# LC_to_ADC.net
KiCad netlist of a schematic drawn in Altium Designer
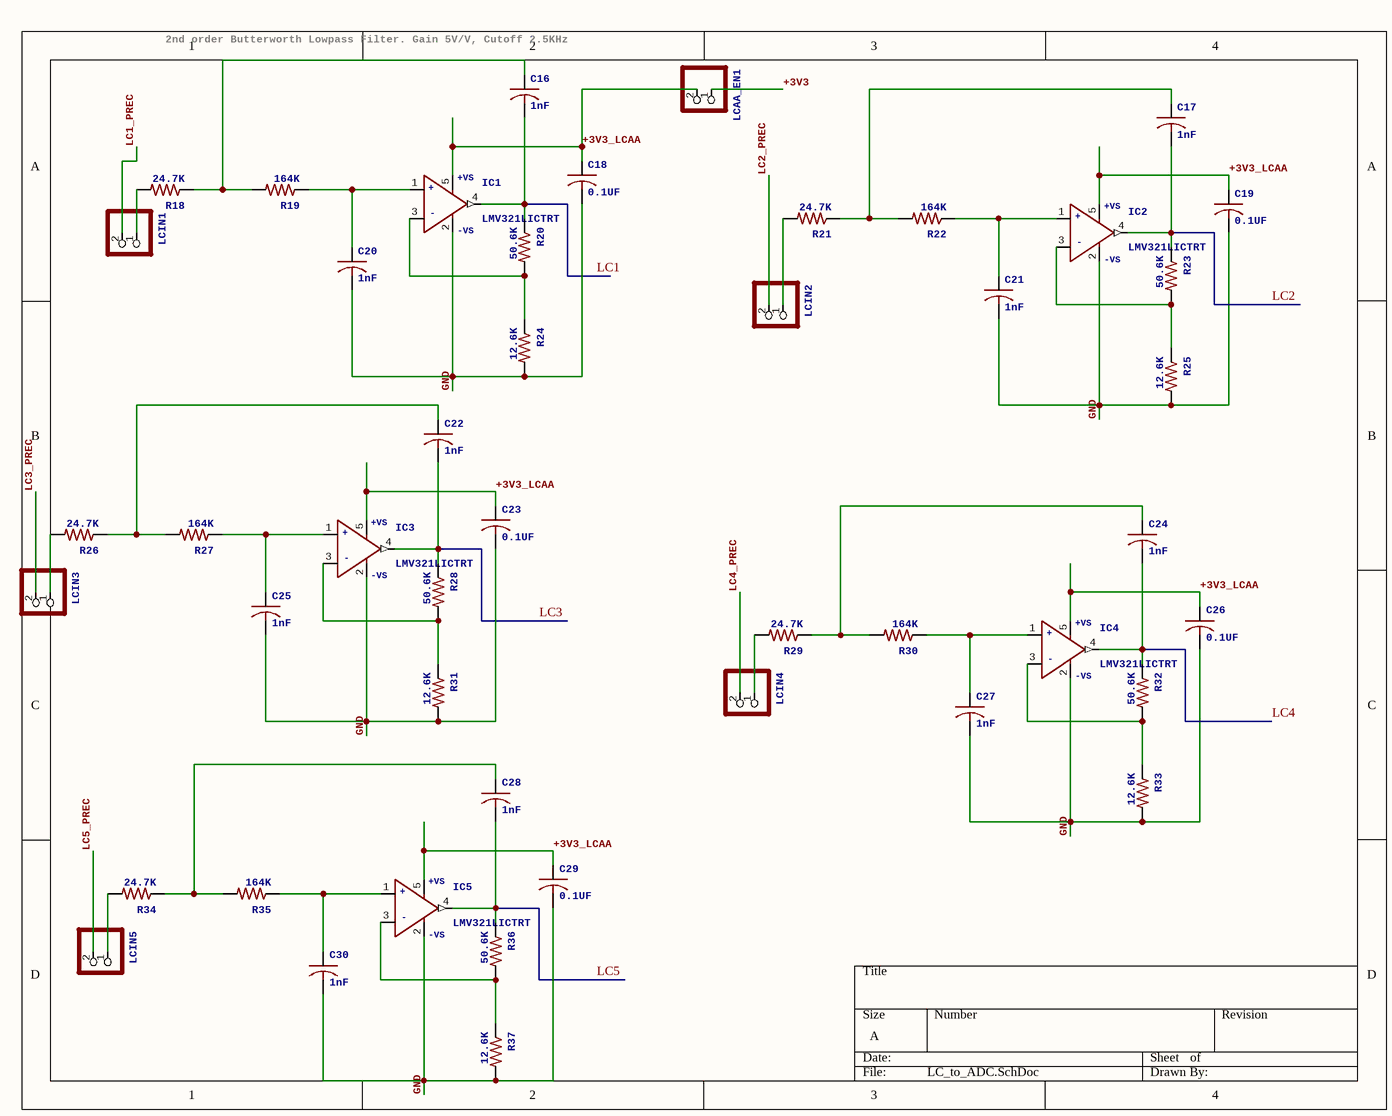
[diagram p0: LC_to_ADC.SchDoc]

(export (version "E")
  (design (tool "Eeschema 10.0.6"))
  (components
    (comp (ref "C16")
      (value "1nF")
      (footprint "CAPCP2012X06N")
      (description "CAPACITOR, American symbol")
      (libsource (lib "rcl") (part "C-USC0805"))
    )
    (comp (ref "C17")
      (value "1nF")
      (footprint "CAPCP2012X06N")
      (description "CAPACITOR, American symbol")
      (libsource (lib "rcl") (part "C-USC0805"))
    )
    (comp (ref "C18")
      (value "0.1UF")
      (footprint "CAPCP2012X06N")
      (description "CAPACITOR, American symbol")
      (libsource (lib "rcl") (part "C-USC0805"))
    )
    (comp (ref "C19")
      (value "0.1UF")
      (footprint "CAPCP2012X06N")
      (description "CAPACITOR, American symbol")
      (libsource (lib "rcl") (part "C-USC0805"))
    )
    (comp (ref "C20")
      (value "1nF")
      (footprint "CAPCP2012X06N")
      (description "CAPACITOR, American symbol")
      (libsource (lib "rcl") (part "C-USC0805"))
    )
    (comp (ref "C21")
      (value "1nF")
      (footprint "CAPCP2012X06N")
      (description "CAPACITOR, American symbol")
      (libsource (lib "rcl") (part "C-USC0805"))
    )
    (comp (ref "C22")
      (value "1nF")
      (footprint "CAPCP2012X06N")
      (description "CAPACITOR, American symbol")
      (libsource (lib "rcl") (part "C-USC0805"))
    )
    (comp (ref "C23")
      (value "0.1UF")
      (footprint "CAPCP2012X06N")
      (description "CAPACITOR, American symbol")
      (libsource (lib "rcl") (part "C-USC0805"))
    )
    (comp (ref "C24")
      (value "1nF")
      (footprint "CAPCP2012X06N")
      (description "CAPACITOR, American symbol")
      (libsource (lib "rcl") (part "C-USC0805"))
    )
    (comp (ref "C25")
      (value "1nF")
      (footprint "CAPCP2012X06N")
      (description "CAPACITOR, American symbol")
      (libsource (lib "rcl") (part "C-USC0805"))
    )
    (comp (ref "C26")
      (value "0.1UF")
      (footprint "CAPCP2012X06N")
      (description "CAPACITOR, American symbol")
      (libsource (lib "rcl") (part "C-USC0805"))
    )
    (comp (ref "C27")
      (value "1nF")
      (footprint "CAPCP2012X06N")
      (description "CAPACITOR, American symbol")
      (libsource (lib "rcl") (part "C-USC0805"))
    )
    (comp (ref "C28")
      (value "1nF")
      (footprint "CAPCP2012X06N")
      (description "CAPACITOR, American symbol")
      (libsource (lib "rcl") (part "C-USC0805"))
    )
    (comp (ref "C29")
      (value "0.1UF")
      (footprint "CAPCP2012X06N")
      (description "CAPACITOR, American symbol")
      (libsource (lib "rcl") (part "C-USC0805"))
    )
    (comp (ref "C30")
      (value "1nF")
      (footprint "CAPCP2012X06N")
      (description "CAPACITOR, American symbol")
      (libsource (lib "rcl") (part "C-USC0805"))
    )
    (comp (ref "IC1")
      (value "LMV321LICTRT")
      (footprint "SOT95P245X110-5N")
      (fields
        (field (name "MF") "ALTERA CORPORATION")
        (field (name "MPN") "AD8065ARTZ-REEL7")
        (field (name "+") "+")
        (field (name "-") "-")
        (field (name "+VS") "+VS")
        (field (name "-VS") "-VS")
        (field (name "LIBRARYNAME") "st-microelectronics-extra")
      )
      (libsource (lib "st-microelectronics-extra") (part "LMV321LICTRT"))
    )
    (comp (ref "IC2")
      (value "LMV321LICTRT")
      (footprint "SOT95P245X110-5N")
      (fields
        (field (name "MF") "ALTERA CORPORATION")
        (field (name "MPN") "AD8065ARTZ-REEL7")
        (field (name "+") "+")
        (field (name "-") "-")
        (field (name "+VS") "+VS")
        (field (name "-VS") "-VS")
        (field (name "LIBRARYNAME") "st-microelectronics-extra")
      )
      (libsource (lib "st-microelectronics-extra") (part "LMV321LICTRT"))
    )
    (comp (ref "IC3")
      (value "LMV321LICTRT")
      (footprint "SOT95P245X110-5N")
      (fields
        (field (name "MF") "ALTERA CORPORATION")
        (field (name "MPN") "AD8065ARTZ-REEL7")
        (field (name "+") "+")
        (field (name "-") "-")
        (field (name "+VS") "+VS")
        (field (name "-VS") "-VS")
        (field (name "LIBRARYNAME") "st-microelectronics-extra")
      )
      (libsource (lib "st-microelectronics-extra") (part "LMV321LICTRT"))
    )
    (comp (ref "IC4")
      (value "LMV321LICTRT")
      (footprint "SOT95P245X110-5N")
      (fields
        (field (name "MF") "ALTERA CORPORATION")
        (field (name "MPN") "AD8065ARTZ-REEL7")
        (field (name "+") "+")
        (field (name "-") "-")
        (field (name "+VS") "+VS")
        (field (name "-VS") "-VS")
        (field (name "LIBRARYNAME") "st-microelectronics-extra")
      )
      (libsource (lib "st-microelectronics-extra") (part "LMV321LICTRT"))
    )
    (comp (ref "IC5")
      (value "LMV321LICTRT")
      (footprint "SOT95P245X110-5N")
      (fields
        (field (name "MF") "ALTERA CORPORATION")
        (field (name "MPN") "AD8065ARTZ-REEL7")
        (field (name "+") "+")
        (field (name "-") "-")
        (field (name "+VS") "+VS")
        (field (name "-VS") "-VS")
        (field (name "LIBRARYNAME") "st-microelectronics-extra")
      )
      (libsource (lib "st-microelectronics-extra") (part "LMV321LICTRT"))
    )
    (comp (ref "LCAA_EN1")
      (value "PINHD-1X2")
      (footprint "MHDR1X2")
      (description "PIN HEADER")
      (fields (field (name "LIBRARYNAME") "pinhead"))
      (libsource (lib "pinhead") (part "PINHD-1X2"))
    )
    (comp (ref "LCIN1")
      (value "PINHD-1X2")
      (footprint "MHDR1X2")
      (description "PIN HEADER")
      (fields (field (name "LIBRARYNAME") "pinhead"))
      (libsource (lib "pinhead") (part "PINHD-1X2"))
    )
    (comp (ref "LCIN2")
      (value "PINHD-1X2")
      (footprint "MHDR1X2")
      (description "PIN HEADER")
      (fields (field (name "LIBRARYNAME") "pinhead"))
      (libsource (lib "pinhead") (part "PINHD-1X2"))
    )
    (comp (ref "LCIN3")
      (value "PINHD-1X2")
      (footprint "MHDR1X2")
      (description "PIN HEADER")
      (fields (field (name "LIBRARYNAME") "pinhead"))
      (libsource (lib "pinhead") (part "PINHD-1X2"))
    )
    (comp (ref "LCIN4")
      (value "PINHD-1X2")
      (footprint "MHDR1X2")
      (description "PIN HEADER")
      (fields (field (name "LIBRARYNAME") "pinhead"))
      (libsource (lib "pinhead") (part "PINHD-1X2"))
    )
    (comp (ref "LCIN5")
      (value "PINHD-1X2")
      (footprint "MHDR1X2")
      (description "PIN HEADER")
      (fields (field (name "LIBRARYNAME") "pinhead"))
      (libsource (lib "pinhead") (part "PINHD-1X2"))
    )
    (comp (ref "R18")
      (value "24.7K")
      (footprint "RESC_0805_2012")
      (description "RESISTOR, American symbol")
      (libsource (lib "rcl") (part "R-US_R0805"))
    )
    (comp (ref "R19")
      (value "164K")
      (footprint "RESC_0805_2012")
      (description "RESISTOR, American symbol")
      (libsource (lib "rcl") (part "R-US_R0805"))
    )
    (comp (ref "R20")
      (value "50.6K")
      (footprint "RESC_0805_2012")
      (description "RESISTOR, American symbol")
      (libsource (lib "rcl") (part "R-US_R0805"))
    )
    (comp (ref "R21")
      (value "24.7K")
      (footprint "RESC_0805_2012")
      (description "RESISTOR, American symbol")
      (libsource (lib "rcl") (part "R-US_R0805"))
    )
    (comp (ref "R22")
      (value "164K")
      (footprint "RESC_0805_2012")
      (description "RESISTOR, American symbol")
      (libsource (lib "rcl") (part "R-US_R0805"))
    )
    (comp (ref "R23")
      (value "50.6K")
      (footprint "RESC_0805_2012")
      (description "RESISTOR, American symbol")
      (libsource (lib "rcl") (part "R-US_R0805"))
    )
    (comp (ref "R24")
      (value "12.6K")
      (footprint "RESC_0805_2012")
      (description "RESISTOR, American symbol")
      (libsource (lib "rcl") (part "R-US_R0805"))
    )
    (comp (ref "R25")
      (value "12.6K")
      (footprint "RESC_0805_2012")
      (description "RESISTOR, American symbol")
      (libsource (lib "rcl") (part "R-US_R0805"))
    )
    (comp (ref "R26")
      (value "24.7K")
      (footprint "RESC_0805_2012")
      (description "RESISTOR, American symbol")
      (libsource (lib "rcl") (part "R-US_R0805"))
    )
    (comp (ref "R27")
      (value "164K")
      (footprint "RESC_0805_2012")
      (description "RESISTOR, American symbol")
      (libsource (lib "rcl") (part "R-US_R0805"))
    )
    (comp (ref "R28")
      (value "50.6K")
      (footprint "RESC_0805_2012")
      (description "RESISTOR, American symbol")
      (libsource (lib "rcl") (part "R-US_R0805"))
    )
    (comp (ref "R29")
      (value "24.7K")
      (footprint "RESC_0805_2012")
      (description "RESISTOR, American symbol")
      (libsource (lib "rcl") (part "R-US_R0805"))
    )
    (comp (ref "R30")
      (value "164K")
      (footprint "RESC_0805_2012")
      (description "RESISTOR, American symbol")
      (libsource (lib "rcl") (part "R-US_R0805"))
    )
    (comp (ref "R31")
      (value "12.6K")
      (footprint "RESC_0805_2012")
      (description "RESISTOR, American symbol")
      (libsource (lib "rcl") (part "R-US_R0805"))
    )
    (comp (ref "R32")
      (value "50.6K")
      (footprint "RESC_0805_2012")
      (description "RESISTOR, American symbol")
      (libsource (lib "rcl") (part "R-US_R0805"))
    )
    (comp (ref "R33")
      (value "12.6K")
      (footprint "RESC_0805_2012")
      (description "RESISTOR, American symbol")
      (libsource (lib "rcl") (part "R-US_R0805"))
    )
    (comp (ref "R34")
      (value "24.7K")
      (footprint "RESC_0805_2012")
      (description "RESISTOR, American symbol")
      (libsource (lib "rcl") (part "R-US_R0805"))
    )
    (comp (ref "R35")
      (value "164K")
      (footprint "RESC_0805_2012")
      (description "RESISTOR, American symbol")
      (libsource (lib "rcl") (part "R-US_R0805"))
    )
    (comp (ref "R36")
      (value "50.6K")
      (footprint "RESC_0805_2012")
      (description "RESISTOR, American symbol")
      (libsource (lib "rcl") (part "R-US_R0805"))
    )
    (comp (ref "R37")
      (value "12.6K")
      (footprint "RESC_0805_2012")
      (description "RESISTOR, American symbol")
      (libsource (lib "rcl") (part "R-US_R0805"))
    )
  )
  (nets
    (net (code "1") (name "/+3V3") (class "Default")
      (node (ref "LCAA_EN1") (pin "1") (pinfunction "1_1") (pintype "passive"))
    )
    (net (code "2") (name "/+3V3_LCAA") (class "Default")
      (node (ref "C18") (pin "1") (pinfunction "1_1") (pintype "passive"))
      (node (ref "C19") (pin "1") (pinfunction "1_1") (pintype "passive"))
      (node (ref "C23") (pin "1") (pinfunction "1_1") (pintype "passive"))
      (node (ref "C26") (pin "1") (pinfunction "1_1") (pintype "passive"))
      (node (ref "C29") (pin "1") (pinfunction "1_1") (pintype "passive"))
      (node (ref "IC1") (pin "5") (pinfunction "+VS_5") (pintype "passive"))
      (node (ref "IC2") (pin "5") (pinfunction "+VS_5") (pintype "passive"))
      (node (ref "IC3") (pin "5") (pinfunction "+VS_5") (pintype "passive"))
      (node (ref "IC4") (pin "5") (pinfunction "+VS_5") (pintype "passive"))
      (node (ref "IC5") (pin "5") (pinfunction "+VS_5") (pintype "passive"))
      (node (ref "LCAA_EN1") (pin "2") (pinfunction "2_2") (pintype "passive"))
    )
    (net (code "3") (name "/GND") (class "Default")
      (node (ref "C18") (pin "2") (pinfunction "2_2") (pintype "passive"))
      (node (ref "C19") (pin "2") (pinfunction "2_2") (pintype "passive"))
      (node (ref "C20") (pin "2") (pinfunction "2_2") (pintype "passive"))
      (node (ref "C21") (pin "2") (pinfunction "2_2") (pintype "passive"))
      (node (ref "C23") (pin "2") (pinfunction "2_2") (pintype "passive"))
      (node (ref "C25") (pin "2") (pinfunction "2_2") (pintype "passive"))
      (node (ref "C26") (pin "2") (pinfunction "2_2") (pintype "passive"))
      (node (ref "C27") (pin "2") (pinfunction "2_2") (pintype "passive"))
      (node (ref "C29") (pin "2") (pinfunction "2_2") (pintype "passive"))
      (node (ref "C30") (pin "2") (pinfunction "2_2") (pintype "passive"))
      (node (ref "IC1") (pin "2") (pinfunction "-VS_2") (pintype "passive"))
      (node (ref "IC2") (pin "2") (pinfunction "-VS_2") (pintype "passive"))
      (node (ref "IC3") (pin "2") (pinfunction "-VS_2") (pintype "passive"))
      (node (ref "IC4") (pin "2") (pinfunction "-VS_2") (pintype "passive"))
      (node (ref "IC5") (pin "2") (pinfunction "-VS_2") (pintype "passive"))
      (node (ref "R24") (pin "2") (pinfunction "2_2") (pintype "passive"))
      (node (ref "R25") (pin "2") (pinfunction "2_2") (pintype "passive"))
      (node (ref "R31") (pin "2") (pinfunction "2_2") (pintype "passive"))
      (node (ref "R33") (pin "2") (pinfunction "2_2") (pintype "passive"))
      (node (ref "R37") (pin "2") (pinfunction "2_2") (pintype "passive"))
    )
    (net (code "4") (name "/LC1") (class "Default")
      (node (ref "C16") (pin "2") (pinfunction "2_2") (pintype "passive"))
      (node (ref "IC1") (pin "4") (pinfunction "OUT_4") (pintype "output"))
      (node (ref "R20") (pin "1") (pinfunction "1_1") (pintype "passive"))
    )
    (net (code "5") (name "/LC1_PREC") (class "Default")
      (node (ref "LCIN1") (pin "2") (pinfunction "2_2") (pintype "passive"))
    )
    (net (code "6") (name "/LC2") (class "Default")
      (node (ref "C17") (pin "2") (pinfunction "2_2") (pintype "passive"))
      (node (ref "IC2") (pin "4") (pinfunction "OUT_4") (pintype "output"))
      (node (ref "R23") (pin "1") (pinfunction "1_1") (pintype "passive"))
    )
    (net (code "7") (name "/LC2_PREC") (class "Default")
      (node (ref "LCIN2") (pin "2") (pinfunction "2_2") (pintype "passive"))
    )
    (net (code "8") (name "/LC3") (class "Default")
      (node (ref "C22") (pin "2") (pinfunction "2_2") (pintype "passive"))
      (node (ref "IC3") (pin "4") (pinfunction "OUT_4") (pintype "output"))
      (node (ref "R28") (pin "1") (pinfunction "1_1") (pintype "passive"))
    )
    (net (code "9") (name "/LC3_PREC") (class "Default")
      (node (ref "LCIN3") (pin "2") (pinfunction "2_2") (pintype "passive"))
    )
    (net (code "10") (name "/LC4") (class "Default")
      (node (ref "C24") (pin "2") (pinfunction "2_2") (pintype "passive"))
      (node (ref "IC4") (pin "4") (pinfunction "OUT_4") (pintype "output"))
      (node (ref "R32") (pin "1") (pinfunction "1_1") (pintype "passive"))
    )
    (net (code "11") (name "/LC4_PREC") (class "Default")
      (node (ref "LCIN4") (pin "2") (pinfunction "2_2") (pintype "passive"))
    )
    (net (code "12") (name "/LC5") (class "Default")
      (node (ref "C28") (pin "2") (pinfunction "2_2") (pintype "passive"))
      (node (ref "IC5") (pin "4") (pinfunction "OUT_4") (pintype "output"))
      (node (ref "R36") (pin "1") (pinfunction "1_1") (pintype "passive"))
    )
    (net (code "13") (name "/LC5_PREC") (class "Default")
      (node (ref "LCIN5") (pin "2") (pinfunction "2_2") (pintype "passive"))
    )
    (net (code "14") (name "Net-(C16-Pad1)") (class "Default")
      (node (ref "C16") (pin "1") (pinfunction "1_1") (pintype "passive"))
      (node (ref "R18") (pin "1") (pinfunction "1_1") (pintype "passive"))
      (node (ref "R19") (pin "2") (pinfunction "2_2") (pintype "passive"))
    )
    (net (code "15") (name "Net-(C17-Pad1)") (class "Default")
      (node (ref "C17") (pin "1") (pinfunction "1_1") (pintype "passive"))
      (node (ref "R21") (pin "1") (pinfunction "1_1") (pintype "passive"))
      (node (ref "R22") (pin "2") (pinfunction "2_2") (pintype "passive"))
    )
    (net (code "16") (name "Net-(C22-Pad1)") (class "Default")
      (node (ref "C22") (pin "1") (pinfunction "1_1") (pintype "passive"))
      (node (ref "R26") (pin "1") (pinfunction "1_1") (pintype "passive"))
      (node (ref "R27") (pin "2") (pinfunction "2_2") (pintype "passive"))
    )
    (net (code "17") (name "Net-(C24-Pad1)") (class "Default")
      (node (ref "C24") (pin "1") (pinfunction "1_1") (pintype "passive"))
      (node (ref "R29") (pin "1") (pinfunction "1_1") (pintype "passive"))
      (node (ref "R30") (pin "2") (pinfunction "2_2") (pintype "passive"))
    )
    (net (code "18") (name "Net-(C28-Pad1)") (class "Default")
      (node (ref "C28") (pin "1") (pinfunction "1_1") (pintype "passive"))
      (node (ref "R34") (pin "1") (pinfunction "1_1") (pintype "passive"))
      (node (ref "R35") (pin "2") (pinfunction "2_2") (pintype "passive"))
    )
    (net (code "19") (name "Net-(IC1-IN+)") (class "Default")
      (node (ref "C20") (pin "1") (pinfunction "1_1") (pintype "passive"))
      (node (ref "IC1") (pin "1") (pinfunction "IN+_1") (pintype "passive"))
      (node (ref "R19") (pin "1") (pinfunction "1_1") (pintype "passive"))
    )
    (net (code "20") (name "Net-(IC1-IN-)") (class "Default")
      (node (ref "IC1") (pin "3") (pinfunction "IN-_3") (pintype "passive"))
      (node (ref "R20") (pin "2") (pinfunction "2_2") (pintype "passive"))
      (node (ref "R24") (pin "1") (pinfunction "1_1") (pintype "passive"))
    )
    (net (code "21") (name "Net-(IC2-IN+)") (class "Default")
      (node (ref "C21") (pin "1") (pinfunction "1_1") (pintype "passive"))
      (node (ref "IC2") (pin "1") (pinfunction "IN+_1") (pintype "passive"))
      (node (ref "R22") (pin "1") (pinfunction "1_1") (pintype "passive"))
    )
    (net (code "22") (name "Net-(IC2-IN-)") (class "Default")
      (node (ref "IC2") (pin "3") (pinfunction "IN-_3") (pintype "passive"))
      (node (ref "R23") (pin "2") (pinfunction "2_2") (pintype "passive"))
      (node (ref "R25") (pin "1") (pinfunction "1_1") (pintype "passive"))
    )
    (net (code "23") (name "Net-(IC3-IN+)") (class "Default")
      (node (ref "C25") (pin "1") (pinfunction "1_1") (pintype "passive"))
      (node (ref "IC3") (pin "1") (pinfunction "IN+_1") (pintype "passive"))
      (node (ref "R27") (pin "1") (pinfunction "1_1") (pintype "passive"))
    )
    (net (code "24") (name "Net-(IC3-IN-)") (class "Default")
      (node (ref "IC3") (pin "3") (pinfunction "IN-_3") (pintype "passive"))
      (node (ref "R28") (pin "2") (pinfunction "2_2") (pintype "passive"))
      (node (ref "R31") (pin "1") (pinfunction "1_1") (pintype "passive"))
    )
    (net (code "25") (name "Net-(IC4-IN+)") (class "Default")
      (node (ref "C27") (pin "1") (pinfunction "1_1") (pintype "passive"))
      (node (ref "IC4") (pin "1") (pinfunction "IN+_1") (pintype "passive"))
      (node (ref "R30") (pin "1") (pinfunction "1_1") (pintype "passive"))
    )
    (net (code "26") (name "Net-(IC4-IN-)") (class "Default")
      (node (ref "IC4") (pin "3") (pinfunction "IN-_3") (pintype "passive"))
      (node (ref "R32") (pin "2") (pinfunction "2_2") (pintype "passive"))
      (node (ref "R33") (pin "1") (pinfunction "1_1") (pintype "passive"))
    )
    (net (code "27") (name "Net-(IC5-IN+)") (class "Default")
      (node (ref "C30") (pin "1") (pinfunction "1_1") (pintype "passive"))
      (node (ref "IC5") (pin "1") (pinfunction "IN+_1") (pintype "passive"))
      (node (ref "R35") (pin "1") (pinfunction "1_1") (pintype "passive"))
    )
    (net (code "28") (name "Net-(IC5-IN-)") (class "Default")
      (node (ref "IC5") (pin "3") (pinfunction "IN-_3") (pintype "passive"))
      (node (ref "R36") (pin "2") (pinfunction "2_2") (pintype "passive"))
      (node (ref "R37") (pin "1") (pinfunction "1_1") (pintype "passive"))
    )
    (net (code "29") (name "Net-(LCIN1-Pad1)") (class "Default")
      (node (ref "LCIN1") (pin "1") (pinfunction "1_1") (pintype "passive"))
      (node (ref "R18") (pin "2") (pinfunction "2_2") (pintype "passive"))
    )
    (net (code "30") (name "Net-(LCIN2-Pad1)") (class "Default")
      (node (ref "LCIN2") (pin "1") (pinfunction "1_1") (pintype "passive"))
      (node (ref "R21") (pin "2") (pinfunction "2_2") (pintype "passive"))
    )
    (net (code "31") (name "Net-(LCIN3-Pad1)") (class "Default")
      (node (ref "LCIN3") (pin "1") (pinfunction "1_1") (pintype "passive"))
      (node (ref "R26") (pin "2") (pinfunction "2_2") (pintype "passive"))
    )
    (net (code "32") (name "Net-(LCIN4-Pad1)") (class "Default")
      (node (ref "LCIN4") (pin "1") (pinfunction "1_1") (pintype "passive"))
      (node (ref "R29") (pin "2") (pinfunction "2_2") (pintype "passive"))
    )
    (net (code "33") (name "Net-(LCIN5-Pad1)") (class "Default")
      (node (ref "LCIN5") (pin "1") (pinfunction "1_1") (pintype "passive"))
      (node (ref "R34") (pin "2") (pinfunction "2_2") (pintype "passive"))
    )
  )
)
